# design.net
KiCad netlist of a schematic drawn in Altium Designer
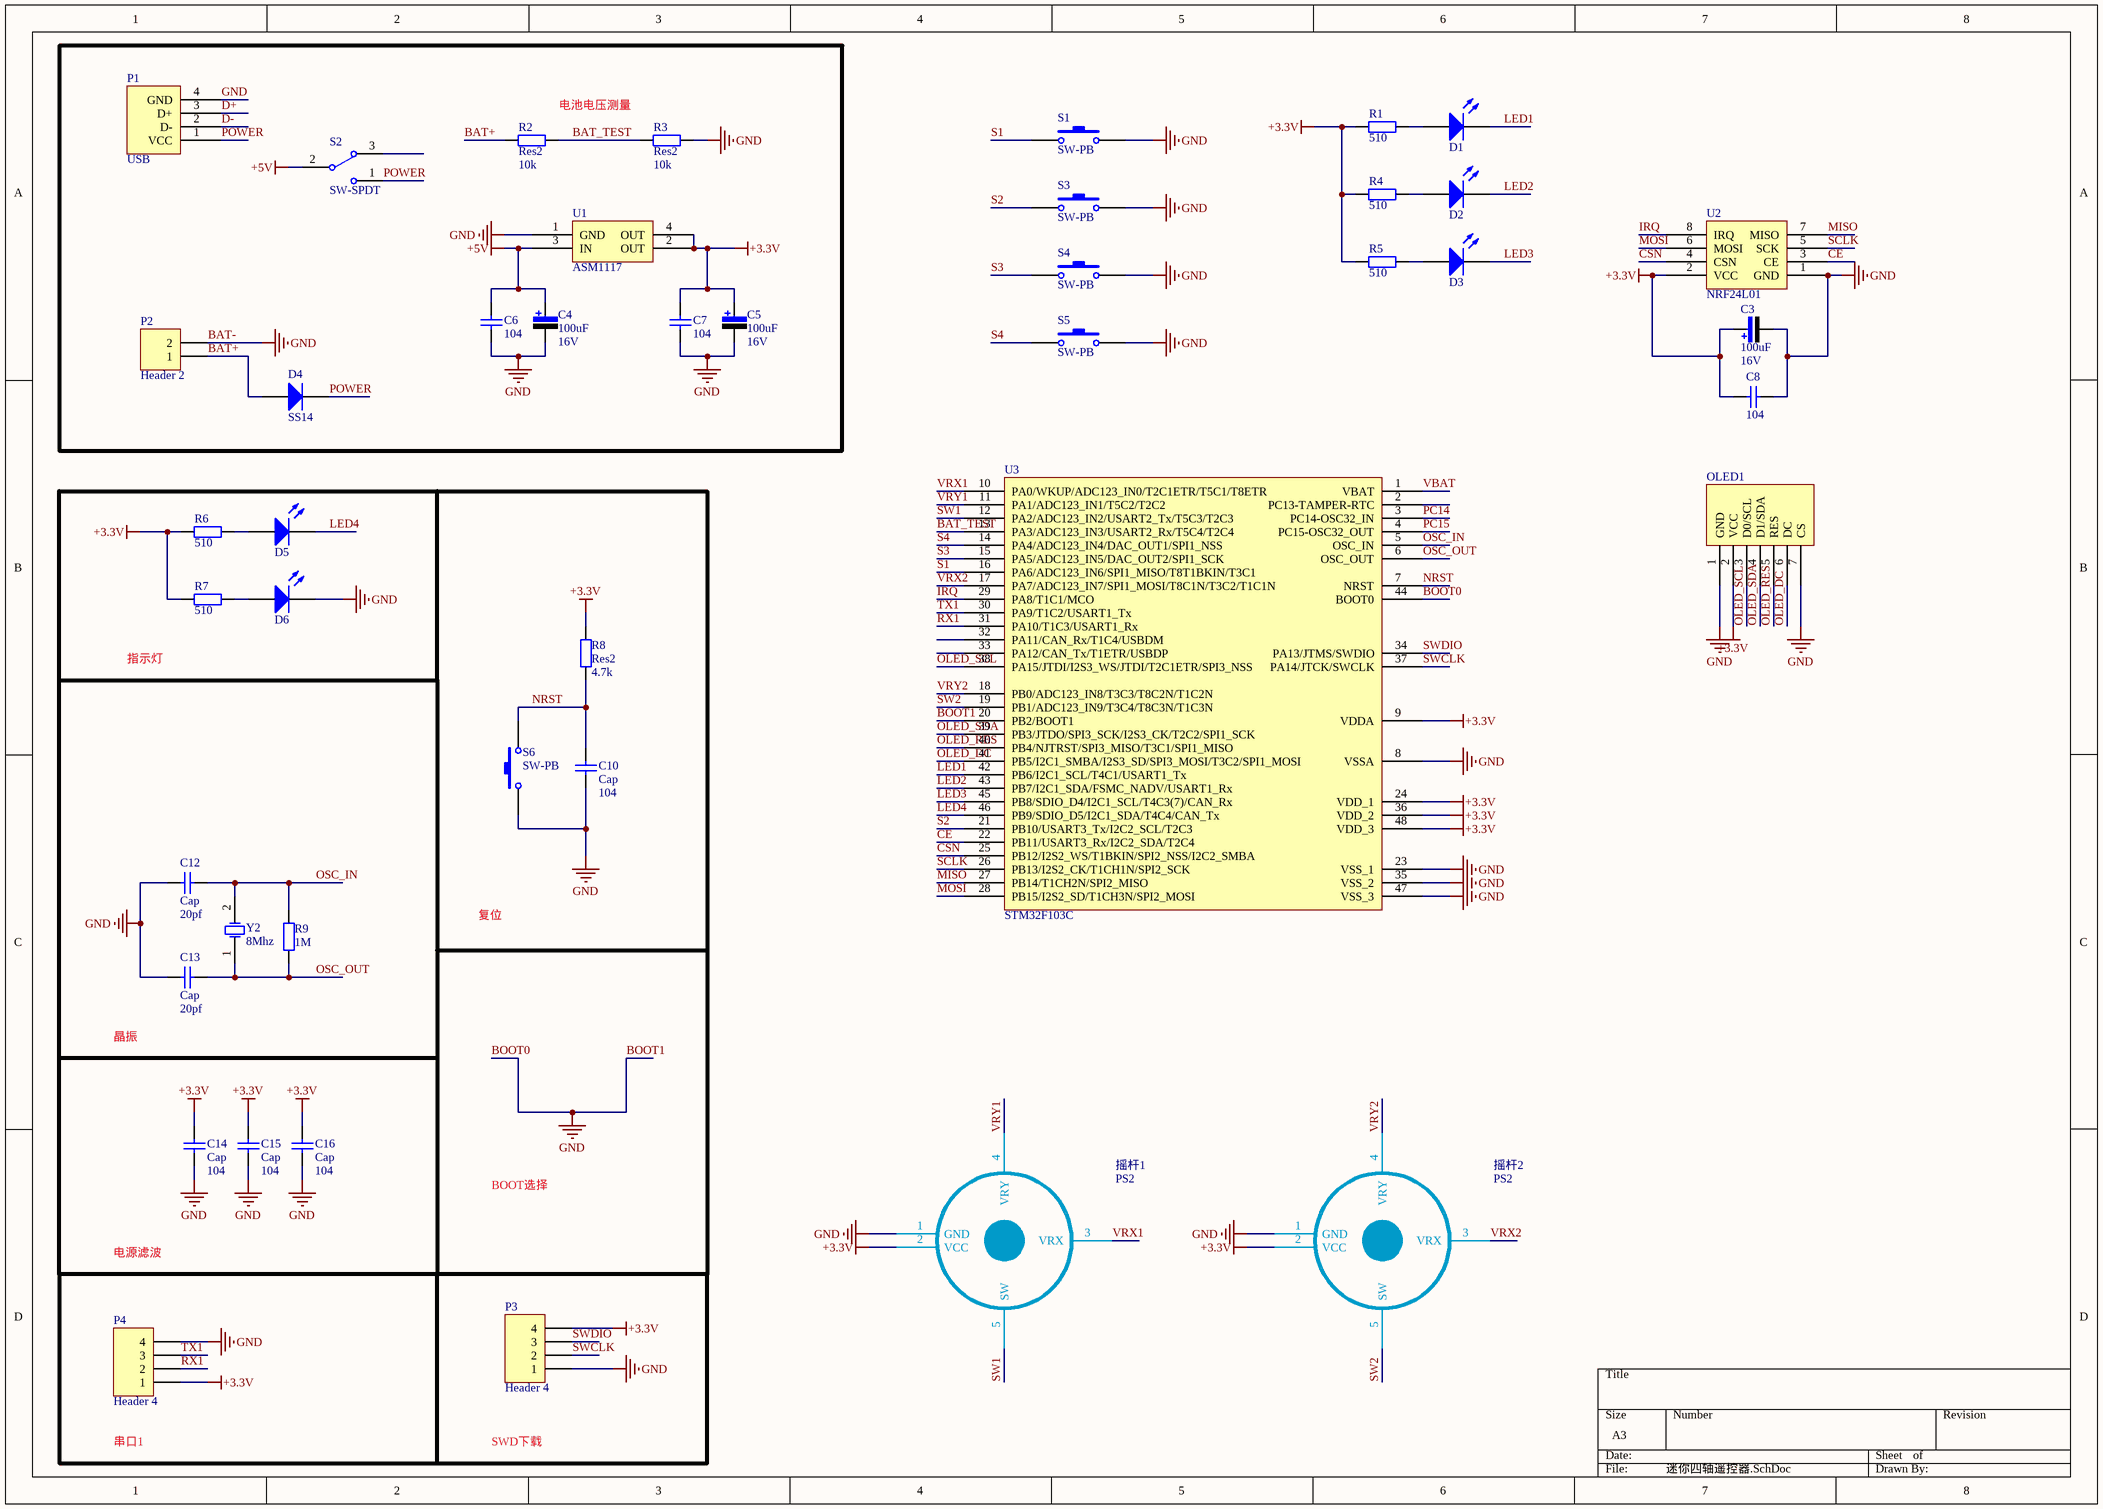
[diagram p0: 迷你四轴遥控器.SchDoc]

(export (version "E")
  (design (tool "Eeschema 10.0.6"))
  (components
    (comp (ref "C3")
      (value "100uF")
      (footprint "CAP-7343")
      (description "极性电解电容")
      (fields
        (field (name "VOL") "16V")
        (field (name "Comment") "Cap Pol")
        (field (name "PUBLISHER") "Altium Limited")
      )
      (libsource (lib "") (part "Cap Pol_1"))
    )
    (comp (ref "C4")
      (value "100uF")
      (footprint "CAP-7343")
      (description "极性电解电容")
      (fields
        (field (name "VOL") "16V")
        (field (name "Comment") "Cap Pol")
        (field (name "PUBLISHER") "Altium Limited")
      )
      (libsource (lib "常用封装") (part "Cap Pol"))
    )
    (comp (ref "C5")
      (value "100uF")
      (footprint "CAP-7343")
      (description "极性电解电容")
      (fields
        (field (name "VOL") "16V")
        (field (name "Comment") "Cap Pol")
        (field (name "PUBLISHER") "Altium Limited")
      )
      (libsource (lib "常用封装") (part "Cap Pol"))
    )
    (comp (ref "C6")
      (value "104")
      (footprint "C-0805")
      (description "无极性电容")
      (fields (field (name "Comment") "Cap") (field (name "PUBLISHER") "Altium Limited"))
      (libsource (lib "常用封装") (part "Cap"))
    )
    (comp (ref "C7")
      (value "104")
      (footprint "C-0805")
      (description "无极性电容")
      (fields (field (name "Comment") "Cap") (field (name "PUBLISHER") "Altium Limited"))
      (libsource (lib "常用封装") (part "Cap"))
    )
    (comp (ref "C8")
      (value "104")
      (footprint "C-0805")
      (description "无极性电容")
      (fields (field (name "Comment") "Cap") (field (name "PUBLISHER") "Altium Limited"))
      (libsource (lib "常用封装") (part "Cap"))
    )
    (comp (ref "C10")
      (value "Cap")
      (footprint "C-0805")
      (description "Capacitor")
      (fields (field (name "ALTIUM_VALUE") "104") (field (name "PUBLISHER") "Altium Limited"))
      (libsource (lib "Miscellaneous Devices") (part "Cap"))
    )
    (comp (ref "C12")
      (value "Cap")
      (footprint "C-0805")
      (description "Capacitor")
      (fields (field (name "ALTIUM_VALUE") "20pf") (field (name "PUBLISHER") "Altium Limited"))
      (libsource (lib "Miscellaneous Devices") (part "Cap"))
    )
    (comp (ref "C13")
      (value "Cap")
      (footprint "C-0805")
      (description "Capacitor")
      (fields (field (name "ALTIUM_VALUE") "20pf") (field (name "PUBLISHER") "Altium Limited"))
      (libsource (lib "Miscellaneous Devices") (part "Cap"))
    )
    (comp (ref "C14")
      (value "Cap")
      (footprint "C-0805")
      (description "Capacitor")
      (fields (field (name "ALTIUM_VALUE") "104") (field (name "PUBLISHER") "Altium Limited"))
      (libsource (lib "Miscellaneous Devices") (part "Cap"))
    )
    (comp (ref "C15")
      (value "Cap")
      (footprint "C-0805")
      (description "Capacitor")
      (fields (field (name "ALTIUM_VALUE") "104") (field (name "PUBLISHER") "Altium Limited"))
      (libsource (lib "Miscellaneous Devices") (part "Cap"))
    )
    (comp (ref "C16")
      (value "Cap")
      (footprint "C-0805")
      (description "Capacitor")
      (fields (field (name "ALTIUM_VALUE") "104") (field (name "PUBLISHER") "Altium Limited"))
      (libsource (lib "Miscellaneous Devices") (part "Cap"))
    )
    (comp (ref "D1")
      (value "LED0")
      (footprint "LED_0805")
      (description "发光二极管")
      (fields (field (name "PUBLISHER") "Altium Limited"))
      (libsource (lib "常用封装") (part "LED0"))
    )
    (comp (ref "D2")
      (value "LED0")
      (footprint "LED_0805")
      (description "发光二极管")
      (fields (field (name "PUBLISHER") "Altium Limited"))
      (libsource (lib "常用封装") (part "LED0"))
    )
    (comp (ref "D3")
      (value "LED0")
      (footprint "LED_0805")
      (description "发光二极管")
      (fields (field (name "PUBLISHER") "Altium Limited"))
      (libsource (lib "常用封装") (part "LED0"))
    )
    (comp (ref "D4")
      (value "SS14")
      (footprint "DO214AA")
      (description "1 Amp General Purpose Rectifier")
      (fields (field (name "PUBLISHER") "Altium Limited"))
      (libsource (lib "Miscellaneous Devices") (part "Diode 1N4007"))
    )
    (comp (ref "D5")
      (value "LED0")
      (footprint "LED_0805")
      (description "发光二极管")
      (fields (field (name "PUBLISHER") "Altium Limited"))
      (libsource (lib "常用封装") (part "LED0"))
    )
    (comp (ref "D6")
      (value "LED0")
      (footprint "LED_0805")
      (description "发光二极管")
      (fields (field (name "PUBLISHER") "Altium Limited"))
      (libsource (lib "常用封装") (part "LED0"))
    )
    (comp (ref "OLED1") (value "OLDE") (footprint "OLED -简版") (libsource (lib "常用封装") (part "OLED-0.96寸")))
    (comp (ref "P1") (value "USB") (footprint "USB_MICRO") (libsource (lib "常用封装") (part "USB")))
    (comp (ref "P2")
      (value "Header 2")
      (footprint "HDR1X2")
      (description "Header, 2-Pin")
      (fields (field (name "PUBLISHER") "Altium Limited"))
      (libsource (lib "Miscellaneous Connectors") (part "Header 2"))
    )
    (comp (ref "P3")
      (value "Header 4")
      (footprint "HDR1X4")
      (description "Header, 4-Pin")
      (fields (field (name "PUBLISHER") "Altium Limited"))
      (libsource (lib "Miscellaneous Connectors") (part "Header 4"))
    )
    (comp (ref "P4")
      (value "Header 4")
      (footprint "HDR1X4")
      (description "Header, 4-Pin")
      (fields (field (name "PUBLISHER") "Altium Limited"))
      (libsource (lib "Miscellaneous Connectors") (part "Header 4"))
    )
    (comp (ref "R1")
      (value "510")
      (footprint "0603-1")
      (description "贴片电阻")
      (fields (field (name "Comment") "Res1") (field (name "PUBLISHER") "Altium Limited"))
      (libsource (lib "") (part "Res1_1"))
    )
    (comp (ref "R2")
      (value "Res2")
      (footprint "0603-1")
      (description "Resistor")
      (fields (field (name "ALTIUM_VALUE") "10k") (field (name "PUBLISHER") "Altium Limited"))
      (libsource (lib "") (part "Res2_1"))
    )
    (comp (ref "R3")
      (value "Res2")
      (footprint "0603-1")
      (description "Resistor")
      (fields (field (name "ALTIUM_VALUE") "10k") (field (name "PUBLISHER") "Altium Limited"))
      (libsource (lib "") (part "Res2_1"))
    )
    (comp (ref "R4")
      (value "510")
      (footprint "0603-1")
      (description "贴片电阻")
      (fields (field (name "Comment") "Res1") (field (name "PUBLISHER") "Altium Limited"))
      (libsource (lib "") (part "Res1_1"))
    )
    (comp (ref "R5")
      (value "510")
      (footprint "0603-1")
      (description "贴片电阻")
      (fields (field (name "Comment") "Res1") (field (name "PUBLISHER") "Altium Limited"))
      (libsource (lib "") (part "Res1_1"))
    )
    (comp (ref "R6")
      (value "510")
      (footprint "0603-1")
      (description "贴片电阻")
      (fields (field (name "Comment") "Res1") (field (name "PUBLISHER") "Altium Limited"))
      (libsource (lib "") (part "Res1_1"))
    )
    (comp (ref "R7")
      (value "510")
      (footprint "0603-1")
      (description "贴片电阻")
      (fields (field (name "Comment") "Res1") (field (name "PUBLISHER") "Altium Limited"))
      (libsource (lib "") (part "Res1_1"))
    )
    (comp (ref "R8")
      (value "Res2")
      (footprint "0603-1")
      (description "Resistor")
      (fields (field (name "ALTIUM_VALUE") "4.7k") (field (name "PUBLISHER") "Altium Limited"))
      (libsource (lib "Miscellaneous Devices") (part "Res2"))
    )
    (comp (ref "R9")
      (value "1M")
      (footprint "0805")
      (description "贴片电阻")
      (fields (field (name "Comment") "Res1") (field (name "PUBLISHER") "Altium Limited"))
      (libsource (lib "常用封装") (part "Res1"))
    )
    (comp (ref "S1")
      (value "SW-PB")
      (footprint "贴片开关")
      (description "Switch")
      (fields (field (name "PUBLISHER") "Altium Limited"))
      (libsource (lib "Miscellaneous Devices") (part "SW-PB"))
    )
    (comp (ref "S2")
      (value "SW-SPDT")
      (footprint "开关-3pin")
      (description "SPDT Subminiature Toggle Switch, Right Angle Mounting, Vertical Actuation")
      (fields (field (name "PUBLISHER") "Altium Limited"))
      (libsource (lib "Miscellaneous Devices") (part "SW-SPDT"))
    )
    (comp (ref "S3")
      (value "SW-PB")
      (footprint "贴片开关")
      (description "Switch")
      (fields (field (name "PUBLISHER") "Altium Limited"))
      (libsource (lib "Miscellaneous Devices") (part "SW-PB"))
    )
    (comp (ref "S4")
      (value "SW-PB")
      (footprint "贴片开关")
      (description "Switch")
      (fields (field (name "PUBLISHER") "Altium Limited"))
      (libsource (lib "Miscellaneous Devices") (part "SW-PB"))
    )
    (comp (ref "S5")
      (value "SW-PB")
      (footprint "贴片开关")
      (description "Switch")
      (fields (field (name "PUBLISHER") "Altium Limited"))
      (libsource (lib "Miscellaneous Devices") (part "SW-PB"))
    )
    (comp (ref "S6")
      (value "SW-PB")
      (footprint "贴片开关")
      (description "Switch")
      (fields (field (name "PUBLISHER") "Altium Limited"))
      (libsource (lib "Miscellaneous Devices") (part "SW-PB"))
    )
    (comp (ref "U1")
      (value "ASM1117")
      (footprint "SOT-223")
      (description "3.3V稳压芯片")
      (libsource (lib "常用封装") (part "ASM1117"))
    )
    (comp (ref "U2") (value "NRF24L01") (footprint "NRF24L01") (libsource (lib "常用封装") (part "NRF24L01")))
    (comp (ref "U3")
      (value "STM32F103C")
      (footprint "LQFP-48_M")
      (description "STM32单片机48引脚")
      (libsource (lib "常用封装") (part "STM32F103C"))
    )
    (comp (ref "Y2")
      (value "8Mhz")
      (footprint "X-SM49")
      (description "Crystal Oscillator")
      (fields (field (name "PUBLISHER") "Altium Limited"))
      (libsource (lib "Miscellaneous Devices") (part "XTAL"))
    )
    (comp (ref "摇杆1") (value "PS2") (footprint "PS2游戏摇杆") (libsource (lib "常用封装") (part "PS2游戏摇杆")))
    (comp (ref "摇杆2") (value "PS2") (footprint "PS2游戏摇杆") (libsource (lib "常用封装") (part "PS2游戏摇杆")))
  )
  (nets
    (net (code "1") (name "+3.3V") (class "Default")
      (node (ref "C14") (pin "2") (pinfunction "2_2") (pintype "passive"))
      (node (ref "C15") (pin "2") (pinfunction "2_2") (pintype "passive"))
      (node (ref "C16") (pin "2") (pinfunction "2_2") (pintype "passive"))
      (node (ref "C3") (pin "1") (pinfunction "1_1") (pintype "passive"))
      (node (ref "C5") (pin "1") (pinfunction "1_1") (pintype "passive"))
      (node (ref "C7") (pin "1") (pinfunction "1_1") (pintype "passive"))
      (node (ref "C8") (pin "1") (pinfunction "1_1") (pintype "passive"))
      (node (ref "OLED1") (pin "2") (pinfunction "VCC_2") (pintype "passive"))
      (node (ref "P3") (pin "4") (pinfunction "4_4") (pintype "passive"))
      (node (ref "P4") (pin "1") (pinfunction "1_1") (pintype "passive"))
      (node (ref "R1") (pin "1") (pinfunction "1_1") (pintype "passive"))
      (node (ref "R4") (pin "1") (pinfunction "1_1") (pintype "passive"))
      (node (ref "R5") (pin "1") (pinfunction "1_1") (pintype "passive"))
      (node (ref "R6") (pin "1") (pinfunction "1_1") (pintype "passive"))
      (node (ref "R7") (pin "1") (pinfunction "1_1") (pintype "passive"))
      (node (ref "R8") (pin "2") (pinfunction "2_2") (pintype "passive"))
      (node (ref "U1") (pin "2") (pinfunction "OUT_2") (pintype "passive"))
      (node (ref "U1") (pin "4") (pinfunction "OUT_4") (pintype "passive"))
      (node (ref "U2") (pin "2") (pinfunction "VCC_2") (pintype "passive"))
      (node (ref "U3") (pin "24") (pinfunction "VDD_1_24") (pintype "passive"))
      (node (ref "U3") (pin "36") (pinfunction "VDD_2_36") (pintype "passive"))
      (node (ref "U3") (pin "48") (pinfunction "VDD_3_48") (pintype "passive"))
      (node (ref "U3") (pin "9") (pinfunction "VDDA_9") (pintype "passive"))
      (node (ref "摇杆1") (pin "2") (pinfunction "VCC_2") (pintype "passive"))
      (node (ref "摇杆2") (pin "2") (pinfunction "VCC_2") (pintype "passive"))
    )
    (net (code "2") (name "+5V") (class "Default")
      (node (ref "C4") (pin "1") (pinfunction "1_1") (pintype "passive"))
      (node (ref "C6") (pin "1") (pinfunction "1_1") (pintype "passive"))
      (node (ref "S2") (pin "2") (pinfunction "2_2") (pintype "passive"))
      (node (ref "U1") (pin "3") (pinfunction "IN_3") (pintype "passive"))
    )
    (net (code "3") (name "/BAT+") (class "Default")
      (node (ref "D4") (pin "1") (pinfunction "A_1") (pintype "passive"))
      (node (ref "P2") (pin "1") (pinfunction "1_1") (pintype "passive"))
      (node (ref "R2") (pin "1") (pinfunction "1_1") (pintype "passive"))
    )
    (net (code "4") (name "/BAT_TEST") (class "Default")
      (node (ref "R2") (pin "2") (pinfunction "2_2") (pintype "passive"))
      (node (ref "R3") (pin "1") (pinfunction "1_1") (pintype "passive"))
      (node (ref "U3") (pin "13") (pinfunction "PA3/ADC123_IN3/USART2_Rx/T5C4/T2C4_13") (pintype "passive"))
    )
    (net (code "5") (name "/CE") (class "Default")
      (node (ref "U2") (pin "3") (pinfunction "CE_3") (pintype "passive"))
      (node (ref "U3") (pin "22") (pinfunction "PB11/USART3_Rx/I2C2_SDA/T2C4_22") (pintype "passive"))
    )
    (net (code "6") (name "/CSN") (class "Default")
      (node (ref "U2") (pin "4") (pinfunction "CSN_4") (pintype "passive"))
      (node (ref "U3") (pin "25") (pinfunction "PB12/I2S2_WS/T1BKIN/SPI2_NSS/I2C2_SMBA_25") (pintype "passive"))
    )
    (net (code "7") (name "/D+") (class "Default")
      (node (ref "P1") (pin "3") (pinfunction "D+_3") (pintype "passive"))
    )
    (net (code "8") (name "/D-") (class "Default")
      (node (ref "P1") (pin "2") (pinfunction "D-_2") (pintype "passive"))
    )
    (net (code "9") (name "/IRQ") (class "Default")
      (node (ref "U2") (pin "8") (pinfunction "IRQ_8") (pintype "passive"))
      (node (ref "U3") (pin "29") (pinfunction "PA8/T1C1/MCO_29") (pintype "passive"))
    )
    (net (code "10") (name "/LED1") (class "Default")
      (node (ref "D1") (pin "2") (pinfunction "K_2") (pintype "passive"))
      (node (ref "U3") (pin "42") (pinfunction "PB6/I2C1_SCL/T4C1/USART1_Tx_42") (pintype "passive"))
    )
    (net (code "11") (name "/LED2") (class "Default")
      (node (ref "D2") (pin "2") (pinfunction "K_2") (pintype "passive"))
      (node (ref "U3") (pin "43") (pinfunction "PB7/I2C1_SDA/FSMC_NADV/USART1_Rx_43") (pintype "passive"))
    )
    (net (code "12") (name "/LED3") (class "Default")
      (node (ref "D3") (pin "2") (pinfunction "K_2") (pintype "passive"))
      (node (ref "U3") (pin "45") (pinfunction "PB8/SDIO_D4/I2C1_SCL/T4C3(7)/CAN_Rx_45") (pintype "passive"))
    )
    (net (code "13") (name "/LED4") (class "Default")
      (node (ref "D5") (pin "2") (pinfunction "K_2") (pintype "passive"))
      (node (ref "U3") (pin "46") (pinfunction "PB9/SDIO_D5/I2C1_SDA/T4C4/CAN_Tx_46") (pintype "passive"))
    )
    (net (code "14") (name "/MISO") (class "Default")
      (node (ref "U2") (pin "7") (pinfunction "MISO_7") (pintype "passive"))
      (node (ref "U3") (pin "27") (pinfunction "PB14/T1CH2N/SPI2_MISO_27") (pintype "passive"))
    )
    (net (code "15") (name "/MOSI") (class "Default")
      (node (ref "U2") (pin "6") (pinfunction "MOSI_6") (pintype "passive"))
      (node (ref "U3") (pin "28") (pinfunction "PB15/I2S2_SD/T1CH3N/SPI2_MOSI_28") (pintype "passive"))
    )
    (net (code "16") (name "/NRST") (class "Default")
      (node (ref "C10") (pin "2") (pinfunction "2_2") (pintype "passive"))
      (node (ref "R8") (pin "1") (pinfunction "1_1") (pintype "passive"))
      (node (ref "S6") (pin "2") (pinfunction "2_2") (pintype "passive"))
      (node (ref "U3") (pin "7") (pinfunction "NRST_7") (pintype "passive"))
    )
    (net (code "17") (name "/OLED_DC") (class "Default")
      (node (ref "OLED1") (pin "6") (pinfunction "DC_6") (pintype "passive"))
      (node (ref "U3") (pin "41") (pinfunction "PB5/I2C1_SMBA/I2S3_SD/SPI3_MOSI/T3C2/SPI1_MOSI_41") (pintype "passive"))
    )
    (net (code "18") (name "/OLED_RES") (class "Default")
      (node (ref "OLED1") (pin "5") (pinfunction "RES_5") (pintype "passive"))
      (node (ref "U3") (pin "40") (pinfunction "PB4/NJTRST/SPI3_MISO/T3C1/SPI1_MISO_40") (pintype "passive"))
    )
    (net (code "19") (name "/OLED_SCL") (class "Default")
      (node (ref "OLED1") (pin "3") (pinfunction "D0/SCL_3") (pintype "passive"))
      (node (ref "U3") (pin "38") (pinfunction "PA15/JTDI/I2S3_WS/JTDI/T2C1ETR/SPI3_NSS_38") (pintype "passive"))
    )
    (net (code "20") (name "/OLED_SDA") (class "Default")
      (node (ref "OLED1") (pin "4") (pinfunction "D1/SDA_4") (pintype "passive"))
      (node (ref "U3") (pin "39") (pinfunction "PB3/JTDO/SPI3_SCK/I2S3_CK/T2C2/SPI1_SCK_39") (pintype "passive"))
    )
    (net (code "21") (name "/OSC_IN") (class "Default")
      (node (ref "C12") (pin "1") (pinfunction "1_1") (pintype "passive"))
      (node (ref "R9") (pin "2") (pinfunction "2_2") (pintype "passive"))
      (node (ref "U3") (pin "5") (pinfunction "OSC_IN_5") (pintype "passive"))
      (node (ref "Y2") (pin "2") (pinfunction "OSC2_2") (pintype "passive"))
    )
    (net (code "22") (name "/OSC_OUT") (class "Default")
      (node (ref "C13") (pin "1") (pinfunction "1_1") (pintype "passive"))
      (node (ref "R9") (pin "1") (pinfunction "1_1") (pintype "passive"))
      (node (ref "U3") (pin "6") (pinfunction "OSC_OUT_6") (pintype "passive"))
      (node (ref "Y2") (pin "1") (pinfunction "OSC1_1") (pintype "passive"))
    )
    (net (code "23") (name "/PC14") (class "Default")
      (node (ref "U3") (pin "3") (pinfunction "PC14-OSC32_IN_3") (pintype "passive"))
    )
    (net (code "24") (name "/PC15") (class "Default")
      (node (ref "U3") (pin "4") (pinfunction "PC15-OSC32_OUT_4") (pintype "passive"))
    )
    (net (code "25") (name "/POWER") (class "Default")
      (node (ref "D4") (pin "2") (pinfunction "K_2") (pintype "passive"))
      (node (ref "P1") (pin "1") (pinfunction "VCC_1") (pintype "passive"))
      (node (ref "S2") (pin "1") (pinfunction "1_1") (pintype "passive"))
    )
    (net (code "26") (name "/RX1") (class "Default")
      (node (ref "P4") (pin "2") (pinfunction "2_2") (pintype "passive"))
      (node (ref "U3") (pin "31") (pinfunction "PA10/T1C3/USART1_Rx_31") (pintype "passive"))
    )
    (net (code "27") (name "/S1") (class "Default")
      (node (ref "S1") (pin "1") (pinfunction "1_1") (pintype "passive"))
      (node (ref "U3") (pin "16") (pinfunction "PA6/ADC123_IN6/SPI1_MISO/T8T1BKIN/T3C1_16") (pintype "passive"))
    )
    (net (code "28") (name "/S2") (class "Default")
      (node (ref "S3") (pin "1") (pinfunction "1_1") (pintype "passive"))
      (node (ref "U3") (pin "21") (pinfunction "PB10/USART3_Tx/I2C2_SCL/T2C3_21") (pintype "passive"))
    )
    (net (code "29") (name "/S3") (class "Default")
      (node (ref "S4") (pin "1") (pinfunction "1_1") (pintype "passive"))
      (node (ref "U3") (pin "15") (pinfunction "PA5/ADC123_IN5/DAC_OUT2/SPI1_SCK_15") (pintype "passive"))
    )
    (net (code "30") (name "/S4") (class "Default")
      (node (ref "S5") (pin "1") (pinfunction "1_1") (pintype "passive"))
      (node (ref "U3") (pin "14") (pinfunction "PA4/ADC123_IN4/DAC_OUT1/SPI1_NSS_14") (pintype "passive"))
    )
    (net (code "31") (name "/SCLK") (class "Default")
      (node (ref "U2") (pin "5") (pinfunction "SCK_5") (pintype "passive"))
      (node (ref "U3") (pin "26") (pinfunction "PB13/I2S2_CK/T1CH1N/SPI2_SCK_26") (pintype "passive"))
    )
    (net (code "32") (name "/SW1") (class "Default")
      (node (ref "U3") (pin "12") (pinfunction "PA2/ADC123_IN2/USART2_Tx/T5C3/T2C3_12") (pintype "passive"))
      (node (ref "摇杆1") (pin "5") (pinfunction "SW_5") (pintype "passive"))
    )
    (net (code "33") (name "/SW2") (class "Default")
      (node (ref "U3") (pin "19") (pinfunction "PB1/ADC123_IN9/T3C4/T8C3N/T1C3N_19") (pintype "passive"))
      (node (ref "摇杆2") (pin "5") (pinfunction "SW_5") (pintype "passive"))
    )
    (net (code "34") (name "/SWCLK") (class "Default")
      (node (ref "P3") (pin "2") (pinfunction "2_2") (pintype "passive"))
      (node (ref "U3") (pin "37") (pinfunction "PA14/JTCK/SWCLK_37") (pintype "passive"))
    )
    (net (code "35") (name "/SWDIO") (class "Default")
      (node (ref "P3") (pin "3") (pinfunction "3_3") (pintype "passive"))
      (node (ref "U3") (pin "34") (pinfunction "PA13/JTMS/SWDIO_34") (pintype "passive"))
    )
    (net (code "36") (name "/TX1") (class "Default")
      (node (ref "P4") (pin "3") (pinfunction "3_3") (pintype "passive"))
      (node (ref "U3") (pin "30") (pinfunction "PA9/T1C2/USART1_Tx_30") (pintype "passive"))
    )
    (net (code "37") (name "/VBAT") (class "Default")
      (node (ref "U3") (pin "1") (pinfunction "VBAT_1") (pintype "passive"))
    )
    (net (code "38") (name "/VRX1") (class "Default")
      (node (ref "U3") (pin "10") (pinfunction "PA0/WKUP/ADC123_IN0/T2C1ETR/T5C1/T8ETR_10") (pintype "passive"))
      (node (ref "摇杆1") (pin "3") (pinfunction "VRX_3") (pintype "passive"))
    )
    (net (code "39") (name "/VRX2") (class "Default")
      (node (ref "U3") (pin "17") (pinfunction "PA7/ADC123_IN7/SPI1_MOSI/T8C1N/T3C2/T1C1N_17") (pintype "passive"))
      (node (ref "摇杆2") (pin "3") (pinfunction "VRX_3") (pintype "passive"))
    )
    (net (code "40") (name "/VRY1") (class "Default")
      (node (ref "U3") (pin "11") (pinfunction "PA1/ADC123_IN1/T5C2/T2C2_11") (pintype "passive"))
      (node (ref "摇杆1") (pin "4") (pinfunction "VRY_4") (pintype "passive"))
    )
    (net (code "41") (name "/VRY2") (class "Default")
      (node (ref "U3") (pin "18") (pinfunction "PB0/ADC123_IN8/T3C3/T8C2N/T1C2N_18") (pintype "passive"))
      (node (ref "摇杆2") (pin "4") (pinfunction "VRY_4") (pintype "passive"))
    )
    (net (code "42") (name "GND") (class "Default")
      (node (ref "C10") (pin "1") (pinfunction "1_1") (pintype "passive"))
      (node (ref "C12") (pin "2") (pinfunction "2_2") (pintype "passive"))
      (node (ref "C13") (pin "2") (pinfunction "2_2") (pintype "passive"))
      (node (ref "C14") (pin "1") (pinfunction "1_1") (pintype "passive"))
      (node (ref "C15") (pin "1") (pinfunction "1_1") (pintype "passive"))
      (node (ref "C16") (pin "1") (pinfunction "1_1") (pintype "passive"))
      (node (ref "C3") (pin "2") (pinfunction "2_2") (pintype "passive"))
      (node (ref "C4") (pin "2") (pinfunction "2_2") (pintype "passive"))
      (node (ref "C5") (pin "2") (pinfunction "2_2") (pintype "passive"))
      (node (ref "C6") (pin "2") (pinfunction "2_2") (pintype "passive"))
      (node (ref "C7") (pin "2") (pinfunction "2_2") (pintype "passive"))
      (node (ref "C8") (pin "2") (pinfunction "2_2") (pintype "passive"))
      (node (ref "D6") (pin "2") (pinfunction "K_2") (pintype "passive"))
      (node (ref "OLED1") (pin "1") (pinfunction "GND_1") (pintype "passive"))
      (node (ref "OLED1") (pin "7") (pinfunction "CS_7") (pintype "passive"))
      (node (ref "P1") (pin "4") (pinfunction "GND_4") (pintype "passive"))
      (node (ref "P2") (pin "2") (pinfunction "2_2") (pintype "passive"))
      (node (ref "P3") (pin "1") (pinfunction "1_1") (pintype "passive"))
      (node (ref "P4") (pin "4") (pinfunction "4_4") (pintype "passive"))
      (node (ref "R3") (pin "2") (pinfunction "2_2") (pintype "passive"))
      (node (ref "S1") (pin "2") (pinfunction "2_2") (pintype "passive"))
      (node (ref "S3") (pin "2") (pinfunction "2_2") (pintype "passive"))
      (node (ref "S4") (pin "2") (pinfunction "2_2") (pintype "passive"))
      (node (ref "S5") (pin "2") (pinfunction "2_2") (pintype "passive"))
      (node (ref "S6") (pin "1") (pinfunction "1_1") (pintype "passive"))
      (node (ref "U1") (pin "1") (pinfunction "GND_1") (pintype "passive"))
      (node (ref "U2") (pin "1") (pinfunction "GND_1") (pintype "passive"))
      (node (ref "U3") (pin "20") (pinfunction "PB2/BOOT1_20") (pintype "passive"))
      (node (ref "U3") (pin "23") (pinfunction "VSS_1_23") (pintype "passive"))
      (node (ref "U3") (pin "35") (pinfunction "VSS_2_35") (pintype "passive"))
      (node (ref "U3") (pin "44") (pinfunction "BOOT0_44") (pintype "passive"))
      (node (ref "U3") (pin "47") (pinfunction "VSS_3_47") (pintype "passive"))
      (node (ref "U3") (pin "8") (pinfunction "VSSA_8") (pintype "passive"))
      (node (ref "摇杆1") (pin "1") (pinfunction "GND_1") (pintype "passive"))
      (node (ref "摇杆2") (pin "1") (pinfunction "GND_1") (pintype "passive"))
    )
    (net (code "43") (name "Net-(D1-A)") (class "Default")
      (node (ref "D1") (pin "1") (pinfunction "A_1") (pintype "passive"))
      (node (ref "R1") (pin "2") (pinfunction "2_2") (pintype "passive"))
    )
    (net (code "44") (name "Net-(D2-A)") (class "Default")
      (node (ref "D2") (pin "1") (pinfunction "A_1") (pintype "passive"))
      (node (ref "R4") (pin "2") (pinfunction "2_2") (pintype "passive"))
    )
    (net (code "45") (name "Net-(D3-A)") (class "Default")
      (node (ref "D3") (pin "1") (pinfunction "A_1") (pintype "passive"))
      (node (ref "R5") (pin "2") (pinfunction "2_2") (pintype "passive"))
    )
    (net (code "46") (name "Net-(D5-A)") (class "Default")
      (node (ref "D5") (pin "1") (pinfunction "A_1") (pintype "passive"))
      (node (ref "R6") (pin "2") (pinfunction "2_2") (pintype "passive"))
    )
    (net (code "47") (name "Net-(D6-A)") (class "Default")
      (node (ref "D6") (pin "1") (pinfunction "A_1") (pintype "passive"))
      (node (ref "R7") (pin "2") (pinfunction "2_2") (pintype "passive"))
    )
    (net (code "48") (name "unconnected-(S2-Pad3)") (class "Default")
      (node (ref "S2") (pin "3") (pinfunction "3_3") (pintype "passive"))
    )
    (net (code "49") (name "unconnected-(U3-PA11{slash}CAN_Rx{slash}T1C4{slash}USBDM-Pad32)") (class "Default")
      (node (ref "U3") (pin "32") (pinfunction "PA11/CAN_Rx/T1C4/USBDM_32") (pintype "passive"))
    )
    (net (code "50") (name "unconnected-(U3-PA12{slash}CAN_Tx{slash}T1ETR{slash}USBDP-Pad33)") (class "Default")
      (node (ref "U3") (pin "33") (pinfunction "PA12/CAN_Tx/T1ETR/USBDP_33") (pintype "passive"))
    )
    (net (code "51") (name "unconnected-(U3-PC13-TAMPER-RTC-Pad2)") (class "Default")
      (node (ref "U3") (pin "2") (pinfunction "PC13-TAMPER-RTC_2") (pintype "passive"))
    )
  )
)
